# BUTTON.net
KiCad netlist of a schematic drawn in Altium Designer
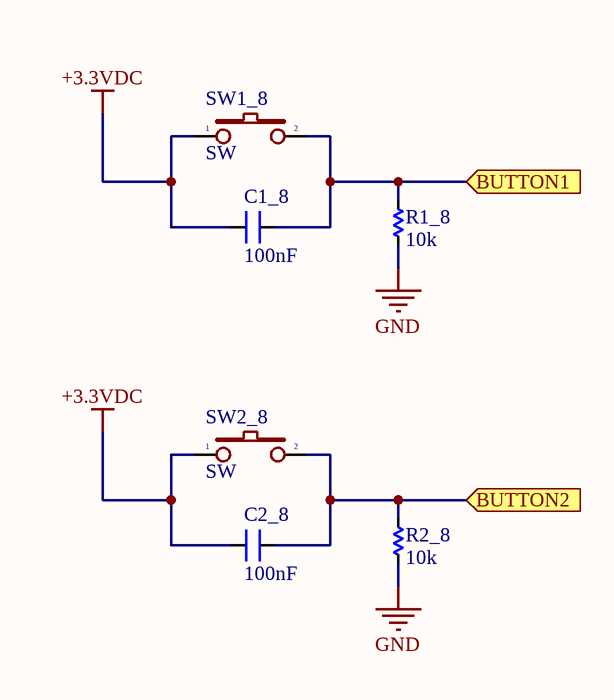
[diagram p0: BUTTON.SchDoc]

(export (version "E")
  (design (tool "Eeschema 10.0.6"))
  (components
    (comp (ref "C1_8")
      (value "100nF")
      (footprint "CN-SMD-0805")
      (libsource (lib "Altium Library") (part "CN"))
    )
    (comp (ref "C2_8")
      (value "100nF")
      (footprint "CN-SMD-0805")
      (libsource (lib "Altium Library") (part "CN"))
    )
    (comp (ref "R1_8")
      (value "10k")
      (footprint "RES-SMD-0805")
      (description "Resistor")
      (fields
        (field (name "MANUFACTURER") "Generic Components")
        (field (name "PUBLISHER") "Altium Hobart Technology Centre")
      )
      (libsource (lib "Altium Library") (part "Res-SMD"))
    )
    (comp (ref "R2_8")
      (value "10k")
      (footprint "RES-SMD-0805")
      (description "Resistor")
      (fields
        (field (name "MANUFACTURER") "Generic Components")
        (field (name "PUBLISHER") "Altium Hobart Technology Centre")
      )
      (libsource (lib "Altium Library") (part "Res-SMD"))
    )
    (comp (ref "SW1_8")
      (value "SW")
      (footprint "SW1-DIP")
      (description "Switch button 2 pin")
      (libsource (lib "Altium Library") (part "SW2"))
    )
    (comp (ref "SW2_8")
      (value "SW")
      (footprint "SW1-DIP")
      (description "Switch button 2 pin")
      (libsource (lib "Altium Library") (part "SW2"))
    )
  )
  (nets
    (net (code "1") (name "+3.3VDC") (class "Default")
      (node (ref "C1_8") (pin "1") (pinfunction "1_1") (pintype "passive"))
      (node (ref "C2_8") (pin "1") (pinfunction "1_1") (pintype "passive"))
      (node (ref "SW1_8") (pin "1") (pinfunction "1_1") (pintype "passive"))
      (node (ref "SW2_8") (pin "1") (pinfunction "1_1") (pintype "passive"))
    )
    (net (code "2") (name "/BUTTON1") (class "Default")
      (node (ref "C1_8") (pin "2") (pinfunction "2_2") (pintype "passive"))
      (node (ref "R1_8") (pin "1") (pinfunction "1_1") (pintype "passive"))
      (node (ref "SW1_8") (pin "2") (pinfunction "2_2") (pintype "passive"))
    )
    (net (code "3") (name "/BUTTON2") (class "Default")
      (node (ref "C2_8") (pin "2") (pinfunction "2_2") (pintype "passive"))
      (node (ref "R2_8") (pin "1") (pinfunction "1_1") (pintype "passive"))
      (node (ref "SW2_8") (pin "2") (pinfunction "2_2") (pintype "passive"))
    )
    (net (code "4") (name "GND") (class "Default")
      (node (ref "R1_8") (pin "2") (pinfunction "2_2") (pintype "passive"))
      (node (ref "R2_8") (pin "2") (pinfunction "2_2") (pintype "passive"))
    )
  )
)
